# example.net
KiCad netlist of a schematic drawn in EAGLE
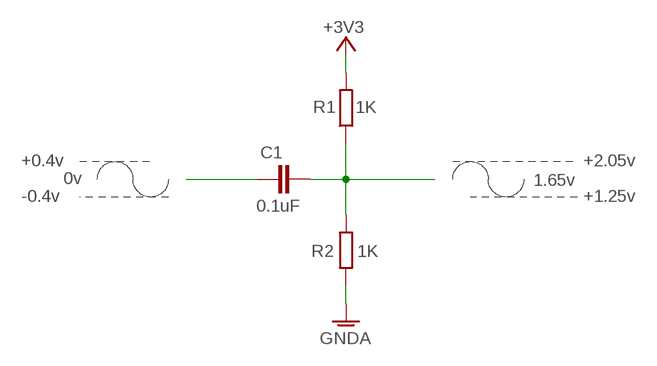
[diagram p0: schematic, sheet 1]

(export (version "E")
  (design (tool "Eeschema 10.0.6"))
  (components
    (comp (ref "C1")
      (value "0.1uF")
      (footprint "eagle-import:C1206")
      (libsource (lib "eagle-import") (part "C-EUC1206"))
    )
    (comp (ref "R1")
      (value "1K")
      (footprint "eagle-import:R1206")
      (libsource (lib "eagle-import") (part "R-EU_R1206"))
    )
    (comp (ref "R2")
      (value "1K")
      (footprint "eagle-import:R1206")
      (libsource (lib "eagle-import") (part "R-EU_R1206"))
    )
  )
  (nets
    (net (code "1") (name "+3V3") (class "Default")
      (node (ref "R1") (pin "2") (pinfunction "2_2") (pintype "passive"))
    )
    (net (code "2") (name "GNDA") (class "Default")
      (node (ref "R2") (pin "1") (pinfunction "1_1") (pintype "passive"))
    )
    (net (code "3") (name "Net-(C1-Pad2)") (class "Default")
      (node (ref "C1") (pin "2") (pinfunction "2_2") (pintype "passive"))
      (node (ref "R1") (pin "1") (pinfunction "1_1") (pintype "passive"))
      (node (ref "R2") (pin "2") (pinfunction "2_2") (pintype "passive"))
    )
    (net (code "4") (name "unconnected-(C1-Pad1)") (class "Default")
      (node (ref "C1") (pin "1") (pinfunction "1_1") (pintype "passive"))
    )
  )
)
